# PowerSupply.net
KiCad netlist of a schematic drawn in Altium Designer
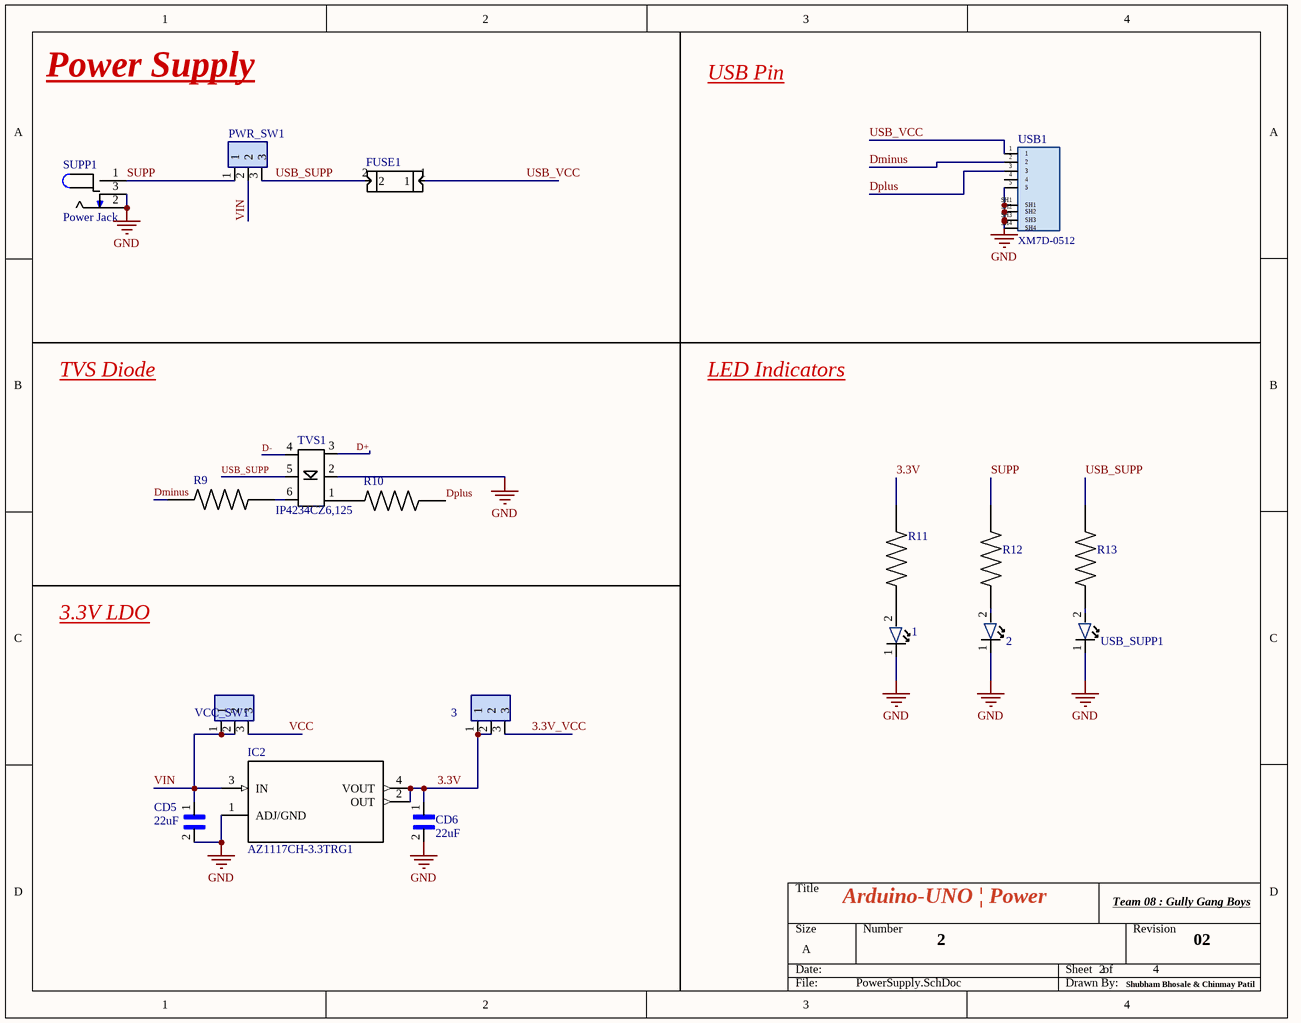
[diagram p0: PowerSupply.SchDoc]

(export (version "E")
  (design (tool "Eeschema 10.0.6"))
  (components
    (comp (ref "1")
      (value "LTST-C150CKT")
      (footprint "LED")
      (description "Red 638nm LED Indication - Discrete 1.8V 1206 (3216 Metric)")
      (fields (field (name "DIGIKEY PART") "160-1167-1-ND"))
      (libsource (lib "brd2_rev2") (part "1206_RED_LED"))
    )
    (comp (ref "2")
      (value "LTST-C150CKT")
      (footprint "LED")
      (description "Red 638nm LED Indication - Discrete 1.8V 1206 (3216 Metric)")
      (fields (field (name "DIGIKEY PART") "160-1167-1-ND"))
      (libsource (lib "brd2_rev2") (part "1206_RED_LED"))
    )
    (comp (ref "3")
      (value "PREC003SAAN-RC")
      (footprint "3_PIN")
      (description "Connector Header Through Hole 3 position 0.100\" (2.54mm)")
      (fields (field (name "DIGIKEY PART") "S1012EC-03-ND"))
      (libsource (lib "brd2_rev2") (part "3_PIN"))
    )
    (comp (ref "CD5")
      (value "22uF")
      (footprint "1206_Passive")
      (description "22µF ±20% 16V Ceramic Capacitor X5R 1206 (3216 Metric)")
      (fields (field (name "DIGIKEY PART") "1276-2728-1-ND"))
      (libsource (lib "brd2_rev2") (part "1206_22uF"))
    )
    (comp (ref "CD6")
      (value "22uF")
      (footprint "1206_Passive")
      (description "22µF ±20% 16V Ceramic Capacitor X5R 1206 (3216 Metric)")
      (fields (field (name "DIGIKEY PART") "1276-2728-1-ND"))
      (libsource (lib "brd2_rev2") (part "1206_22uF"))
    )
    (comp (ref "FUSE1")
      (value "MF-MSMF050-2")
      (footprint "FUSE")
      (description "Polymeric PTC Resettable Fuse 15V 500mA Ih Surface Mount 1812 (4532 Metric), Concave")
      (fields (field (name "DIGIKEY PART") "MF-MSMF050-2CT-ND"))
      (libsource (lib "brd2_rev2") (part "Fuse"))
    )
    (comp (ref "IC2")
      (value "AZ1117CH-3.3TRG1")
      (footprint "LDO")
      (description "Linear Voltage Regulator IC Positive Fixed 1 Output 1A SOT-223")
      (fields (field (name "DIGIKEY PART") "AZ1117CH-3.3TRG1DICT-ND"))
      (libsource (lib "brd2_rev2") (part "3.3V_LDO"))
    )
    (comp (ref "PWR_SW1")
      (value "PREC003SAAN-RC")
      (footprint "3_PIN")
      (description "Connector Header Through Hole 3 position 0.100\" (2.54mm)")
      (fields (field (name "DIGIKEY PART") "S1012EC-03-ND"))
      (libsource (lib "brd2_rev2") (part "3_PIN"))
    )
    (comp (ref "R9")
      (value "RMCF1206JT300R‎")
      (footprint "1206_Passive")
      (description "300 Ohms ±5% 0.25W, 1/4W Chip Resistor 1206 (3216 Metric) Automotive AEC-Q200 Thick Film")
      (fields (field (name "DIGIKEY PART") "RMCF1206JT300RCT-ND"))
      (libsource (lib "brd2_rev2") (part "1206_300Ohm"))
    )
    (comp (ref "R10")
      (value "RMCF1206JT300R‎")
      (footprint "1206_Passive")
      (description "300 Ohms ±5% 0.25W, 1/4W Chip Resistor 1206 (3216 Metric) Automotive AEC-Q200 Thick Film")
      (fields (field (name "DIGIKEY PART") "RMCF1206JT300RCT-ND"))
      (libsource (lib "brd2_rev2") (part "1206_300Ohm"))
    )
    (comp (ref "R11")
      (value "RNCP1206FTD1K00")
      (footprint "1206_Passive")
      (description "1 kOhms ±1% 0.5W, 1/2W Chip Resistor 1206 (3216 Metric) Anti-Sulfur, Moisture Resistant Thin Film")
      (fields (field (name "DIGIKEY PART") "RNCP1206FTD1K00CT-ND"))
      (libsource (lib "brd2_rev2") (part "1206_1K"))
    )
    (comp (ref "R12")
      (value "RNCP1206FTD1K00")
      (footprint "1206_Passive")
      (description "1 kOhms ±1% 0.5W, 1/2W Chip Resistor 1206 (3216 Metric) Anti-Sulfur, Moisture Resistant Thin Film")
      (fields (field (name "DIGIKEY PART") "RNCP1206FTD1K00CT-ND"))
      (libsource (lib "brd2_rev2") (part "1206_1K"))
    )
    (comp (ref "R13")
      (value "RNCP1206FTD1K00")
      (footprint "1206_Passive")
      (description "1 kOhms ±1% 0.5W, 1/2W Chip Resistor 1206 (3216 Metric) Anti-Sulfur, Moisture Resistant Thin Film")
      (fields (field (name "DIGIKEY PART") "RNCP1206FTD1K00CT-ND"))
      (libsource (lib "brd2_rev2") (part "1206_1K"))
    )
    (comp (ref "SUPP1")
      (value "Power Jack")
      (footprint "Power_Jack")
      (description "Power Barrel Connector Jack 2.10mm ID (0.083\"), 5.50mm OD (0.217\") Through Hole, Right Angle")
      (fields (field (name "DIGIKEY PART") "CP-102A-ND"))
      (libsource (lib "brd2_rev2") (part "Power Jack"))
    )
    (comp (ref "TVS1")
      (value "IP4234CZ6,125")
      (footprint "TVS")
      (description "Clamp Ipp Tvs Diode Surface Mount 6-TSOP")
      (fields (field (name "DIGIKEY PART") "1727-4717-1-ND"))
      (libsource (lib "brd2_rev2") (part "TVS_Diode"))
    )
    (comp (ref "USB1")
      (value "XM7D-0512")
      (footprint "USB")
      (description "USB - mini B USB 2.0 Receptacle Connector 5 Position Through Hole, Right Angle")
      (fields (field (name "DIGIKEY PART") "OR1205-ND"))
      (libsource (lib "brd2_rev2") (part "USB"))
    )
    (comp (ref "USB_SUPP1")
      (value "LTST-C150CKT")
      (footprint "LED")
      (description "Red 638nm LED Indication - Discrete 1.8V 1206 (3216 Metric)")
      (fields (field (name "DIGIKEY PART") "160-1167-1-ND"))
      (libsource (lib "brd2_rev2") (part "1206_RED_LED"))
    )
    (comp (ref "VCC_SW1")
      (value "PREC003SAAN-RC")
      (footprint "3_PIN")
      (description "Connector Header Through Hole 3 position 0.100\" (2.54mm)")
      (fields (field (name "DIGIKEY PART") "S1012EC-03-ND"))
      (libsource (lib "brd2_rev2") (part "3_PIN"))
    )
  )
  (nets
    (net (code "1") (name "/3.3V") (class "Default")
      (node (ref "3") (pin "1") (pinfunction "1_1") (pintype "passive"))
      (node (ref "3") (pin "2") (pinfunction "2_2") (pintype "passive"))
      (node (ref "CD6") (pin "1") (pinfunction "1_1") (pintype "passive"))
      (node (ref "IC2") (pin "2") (pinfunction "OUT_2") (pintype "output"))
      (node (ref "IC2") (pin "4") (pinfunction "VOUT_4") (pintype "output"))
      (node (ref "R11") (pin "2") (pinfunction "2_2") (pintype "passive"))
    )
    (net (code "2") (name "/3.3V_VCC") (class "Default")
      (node (ref "3") (pin "3") (pinfunction "3_3") (pintype "passive"))
    )
    (net (code "4") (name "/D+") (class "Default")
      (node (ref "TVS1") (pin "3") (pinfunction "3_3") (pintype "passive"))
    )
    (net (code "5") (name "/D-") (class "Default")
      (node (ref "TVS1") (pin "4") (pinfunction "4_4") (pintype "passive"))
    )
    (net (code "6") (name "/Dminus") (class "Default")
      (node (ref "R9") (pin "1") (pinfunction "1_1") (pintype "passive"))
      (node (ref "USB1") (pin "2") (pinfunction "2_2") (pintype "passive"))
    )
    (net (code "7") (name "/Dplus") (class "Default")
      (node (ref "R10") (pin "2") (pinfunction "2_2") (pintype "passive"))
      (node (ref "USB1") (pin "3") (pinfunction "3_3") (pintype "passive"))
    )
    (net (code "8") (name "/SUPP") (class "Default")
      (node (ref "PWR_SW1") (pin "1") (pinfunction "1_1") (pintype "passive"))
      (node (ref "R12") (pin "1") (pinfunction "1_1") (pintype "passive"))
      (node (ref "SUPP1") (pin "1") (pinfunction "1_1") (pintype "passive"))
    )
    (net (code "9") (name "/USB_SUPP") (class "Default")
      (node (ref "FUSE1") (pin "2") (pinfunction "2_2") (pintype "passive"))
      (node (ref "PWR_SW1") (pin "3") (pinfunction "3_3") (pintype "passive"))
      (node (ref "R13") (pin "1") (pinfunction "1_1") (pintype "passive"))
      (node (ref "TVS1") (pin "5") (pinfunction "5_5") (pintype "passive"))
    )
    (net (code "10") (name "/USB_VCC") (class "Default")
      (node (ref "FUSE1") (pin "1") (pinfunction "1_1") (pintype "passive"))
      (node (ref "USB1") (pin "1") (pinfunction "1_1") (pintype "passive"))
    )
    (net (code "11") (name "/VCC") (class "Default")
      (node (ref "VCC_SW1") (pin "3") (pinfunction "3_3") (pintype "passive"))
    )
    (net (code "12") (name "/VIN") (class "Default")
      (node (ref "CD5") (pin "1") (pinfunction "1_1") (pintype "passive"))
      (node (ref "IC2") (pin "3") (pinfunction "IN_3") (pintype "input"))
      (node (ref "PWR_SW1") (pin "2") (pinfunction "2_2") (pintype "passive"))
      (node (ref "VCC_SW1") (pin "1") (pinfunction "1_1") (pintype "passive"))
      (node (ref "VCC_SW1") (pin "2") (pinfunction "2_2") (pintype "passive"))
    )
    (net (code "13") (name "GND") (class "Default")
      (node (ref "1") (pin "1") (pinfunction "1_1") (pintype "passive"))
      (node (ref "2") (pin "1") (pinfunction "1_1") (pintype "passive"))
      (node (ref "CD5") (pin "2") (pinfunction "2_2") (pintype "passive"))
      (node (ref "CD6") (pin "2") (pinfunction "2_2") (pintype "passive"))
      (node (ref "IC2") (pin "1") (pinfunction "ADJ/GND_1") (pintype "passive"))
      (node (ref "SUPP1") (pin "2") (pinfunction "2_2") (pintype "passive"))
      (node (ref "SUPP1") (pin "3") (pinfunction "3_3") (pintype "passive"))
      (node (ref "TVS1") (pin "2") (pinfunction "2_2") (pintype "passive"))
      (node (ref "USB1") (pin "5") (pinfunction "5_5") (pintype "passive"))
      (node (ref "USB1") (pin "SH1") (pinfunction "SH1_SH1") (pintype "passive"))
      (node (ref "USB1") (pin "SH2") (pinfunction "SH2_SH2") (pintype "passive"))
      (node (ref "USB1") (pin "SH3") (pinfunction "SH3_SH3") (pintype "passive"))
      (node (ref "USB1") (pin "SH4") (pinfunction "SH4_SH4") (pintype "passive"))
      (node (ref "USB_SUPP1") (pin "1") (pinfunction "1_1") (pintype "passive"))
    )
    (net (code "14") (name "Net-(1-Pad2)") (class "Default")
      (node (ref "1") (pin "2") (pinfunction "2_2") (pintype "passive"))
      (node (ref "R11") (pin "1") (pinfunction "1_1") (pintype "passive"))
    )
    (net (code "15") (name "Net-(2-Pad2)") (class "Default")
      (node (ref "2") (pin "2") (pinfunction "2_2") (pintype "passive"))
      (node (ref "R12") (pin "2") (pinfunction "2_2") (pintype "passive"))
    )
    (net (code "16") (name "Net-(R9-Pad2)") (class "Default")
      (node (ref "R9") (pin "2") (pinfunction "2_2") (pintype "passive"))
      (node (ref "TVS1") (pin "6") (pinfunction "6_6") (pintype "passive"))
    )
    (net (code "17") (name "Net-(R10-Pad1)") (class "Default")
      (node (ref "R10") (pin "1") (pinfunction "1_1") (pintype "passive"))
      (node (ref "TVS1") (pin "1") (pinfunction "1_1") (pintype "passive"))
    )
    (net (code "18") (name "Net-(R13-Pad2)") (class "Default")
      (node (ref "R13") (pin "2") (pinfunction "2_2") (pintype "passive"))
      (node (ref "USB_SUPP1") (pin "2") (pinfunction "2_2") (pintype "passive"))
    )
    (net (code "19") (name "unconnected-(USB1-Pad4)") (class "Default")
      (node (ref "USB1") (pin "4") (pinfunction "4_4") (pintype "passive"))
    )
  )
)
